# Access_System_Bmduino.net
KiCad netlist of a schematic drawn in Altium Designer
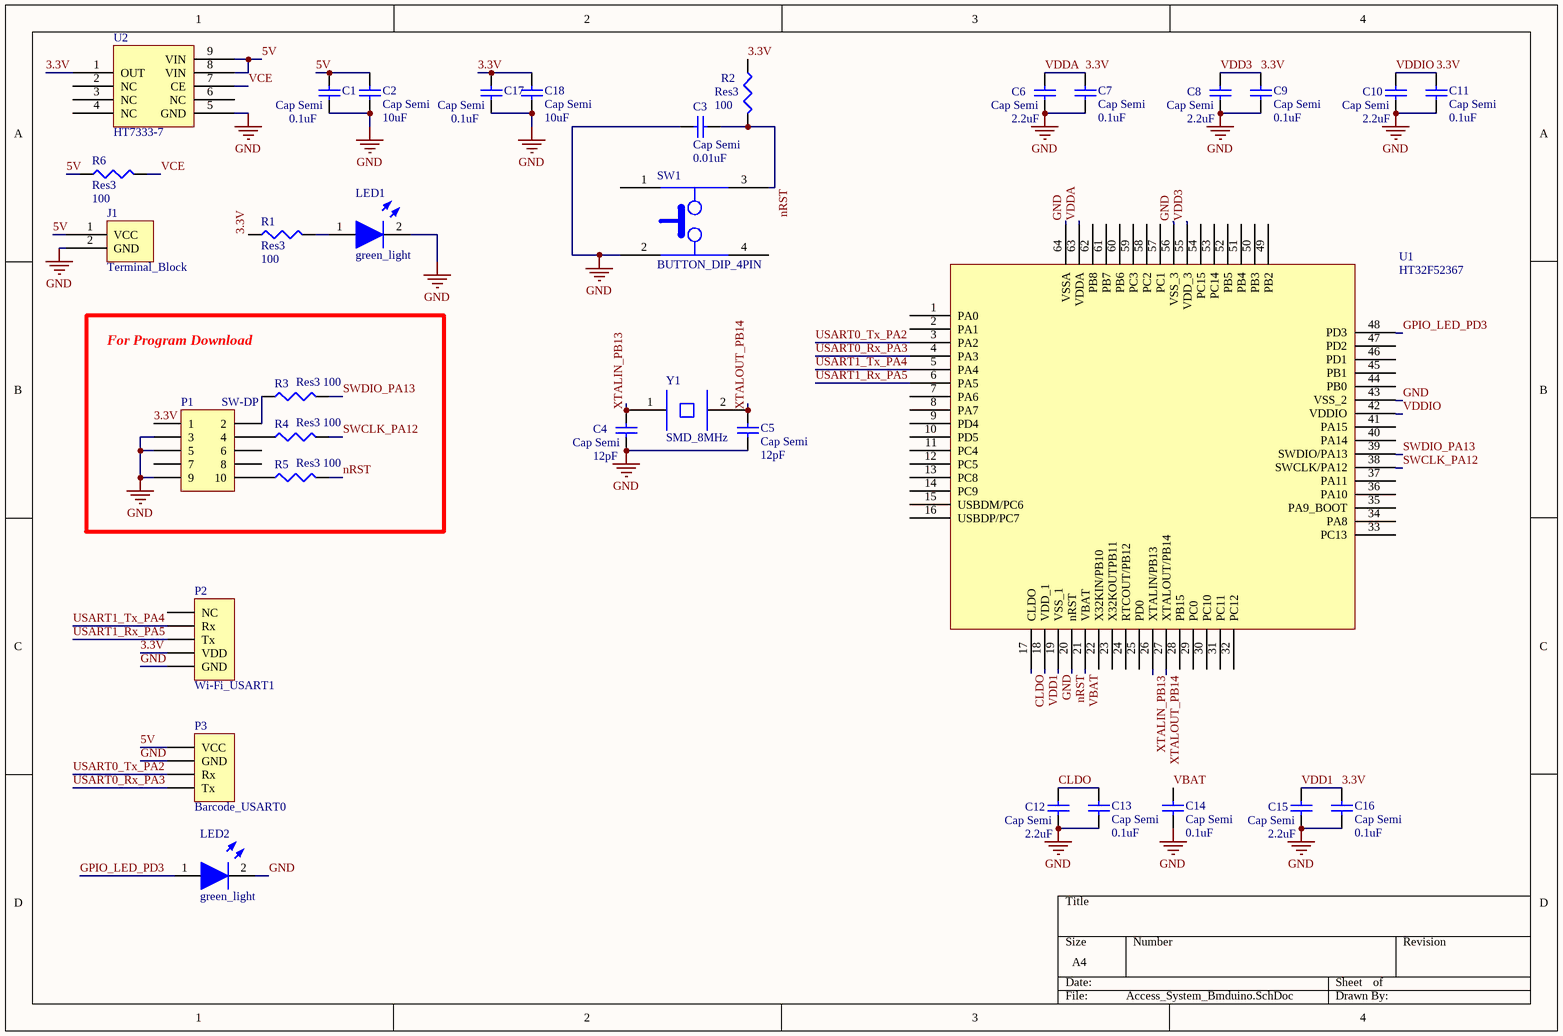
[diagram p0: Access_System_Bmduino.SchDoc]

(export (version "E")
  (design (tool "Eeschema 10.0.6"))
  (components
    (comp (ref "C1")
      (value "Cap Semi")
      (footprint "1608[0603]")
      (description "Capacitor (Semiconductor SIM Model)")
      (fields (field (name "ALTIUM_VALUE") "0.1uF") (field (name "PUBLISHER") "Altium Limited"))
      (libsource (lib "Miscellaneous Devices") (part "Cap Semi"))
    )
    (comp (ref "C2")
      (value "Cap Semi")
      (footprint "1608[0603]")
      (description "Capacitor (Semiconductor SIM Model)")
      (fields (field (name "ALTIUM_VALUE") "10uF") (field (name "PUBLISHER") "Altium Limited"))
      (libsource (lib "Miscellaneous Devices") (part "Cap Semi"))
    )
    (comp (ref "C3")
      (value "Cap Semi")
      (footprint "1608[0603]")
      (description "Capacitor (Semiconductor SIM Model)")
      (fields (field (name "ALTIUM_VALUE") "0.01uF") (field (name "PUBLISHER") "Altium Limited"))
      (libsource (lib "Miscellaneous Devices") (part "Cap Semi"))
    )
    (comp (ref "C4")
      (value "Cap Semi")
      (footprint "1608[0603]")
      (description "Capacitor (Semiconductor SIM Model)")
      (fields (field (name "ALTIUM_VALUE") "12pF") (field (name "PUBLISHER") "Altium Limited"))
      (libsource (lib "Miscellaneous Devices") (part "Cap Semi"))
    )
    (comp (ref "C5")
      (value "Cap Semi")
      (footprint "1608[0603]")
      (description "Capacitor (Semiconductor SIM Model)")
      (fields (field (name "ALTIUM_VALUE") "12pF") (field (name "PUBLISHER") "Altium Limited"))
      (libsource (lib "Miscellaneous Devices") (part "Cap Semi"))
    )
    (comp (ref "C6")
      (value "Cap Semi")
      (footprint "1608[0603]")
      (description "Capacitor (Semiconductor SIM Model)")
      (fields (field (name "ALTIUM_VALUE") "2.2uF") (field (name "PUBLISHER") "Altium Limited"))
      (libsource (lib "Miscellaneous Devices") (part "Cap Semi"))
    )
    (comp (ref "C7")
      (value "Cap Semi")
      (footprint "1608[0603]")
      (description "Capacitor (Semiconductor SIM Model)")
      (fields (field (name "ALTIUM_VALUE") "0.1uF") (field (name "PUBLISHER") "Altium Limited"))
      (libsource (lib "Miscellaneous Devices") (part "Cap Semi"))
    )
    (comp (ref "C8")
      (value "Cap Semi")
      (footprint "1608[0603]")
      (description "Capacitor (Semiconductor SIM Model)")
      (fields (field (name "ALTIUM_VALUE") "2.2uF") (field (name "PUBLISHER") "Altium Limited"))
      (libsource (lib "Miscellaneous Devices") (part "Cap Semi"))
    )
    (comp (ref "C9")
      (value "Cap Semi")
      (footprint "1608[0603]")
      (description "Capacitor (Semiconductor SIM Model)")
      (fields (field (name "ALTIUM_VALUE") "0.1uF") (field (name "PUBLISHER") "Altium Limited"))
      (libsource (lib "Miscellaneous Devices") (part "Cap Semi"))
    )
    (comp (ref "C10")
      (value "Cap Semi")
      (footprint "1608[0603]")
      (description "Capacitor (Semiconductor SIM Model)")
      (fields (field (name "ALTIUM_VALUE") "2.2uF") (field (name "PUBLISHER") "Altium Limited"))
      (libsource (lib "Miscellaneous Devices") (part "Cap Semi"))
    )
    (comp (ref "C11")
      (value "Cap Semi")
      (footprint "1608[0603]")
      (description "Capacitor (Semiconductor SIM Model)")
      (fields (field (name "ALTIUM_VALUE") "0.1uF") (field (name "PUBLISHER") "Altium Limited"))
      (libsource (lib "Miscellaneous Devices") (part "Cap Semi"))
    )
    (comp (ref "C12")
      (value "Cap Semi")
      (footprint "1608[0603]")
      (description "Capacitor (Semiconductor SIM Model)")
      (fields (field (name "ALTIUM_VALUE") "2.2uF") (field (name "PUBLISHER") "Altium Limited"))
      (libsource (lib "Miscellaneous Devices") (part "Cap Semi"))
    )
    (comp (ref "C13")
      (value "Cap Semi")
      (footprint "1608[0603]")
      (description "Capacitor (Semiconductor SIM Model)")
      (fields (field (name "ALTIUM_VALUE") "0.1uF") (field (name "PUBLISHER") "Altium Limited"))
      (libsource (lib "Miscellaneous Devices") (part "Cap Semi"))
    )
    (comp (ref "C14")
      (value "Cap Semi")
      (footprint "1608[0603]")
      (description "Capacitor (Semiconductor SIM Model)")
      (fields (field (name "ALTIUM_VALUE") "0.1uF") (field (name "PUBLISHER") "Altium Limited"))
      (libsource (lib "Miscellaneous Devices") (part "Cap Semi"))
    )
    (comp (ref "C15")
      (value "Cap Semi")
      (footprint "1608[0603]")
      (description "Capacitor (Semiconductor SIM Model)")
      (fields (field (name "ALTIUM_VALUE") "2.2uF") (field (name "PUBLISHER") "Altium Limited"))
      (libsource (lib "Miscellaneous Devices") (part "Cap Semi"))
    )
    (comp (ref "C16")
      (value "Cap Semi")
      (footprint "1608[0603]")
      (description "Capacitor (Semiconductor SIM Model)")
      (fields (field (name "ALTIUM_VALUE") "0.1uF") (field (name "PUBLISHER") "Altium Limited"))
      (libsource (lib "Miscellaneous Devices") (part "Cap Semi"))
    )
    (comp (ref "C17")
      (value "Cap Semi")
      (footprint "1608[0603]")
      (description "Capacitor (Semiconductor SIM Model)")
      (fields (field (name "ALTIUM_VALUE") "0.1uF") (field (name "PUBLISHER") "Altium Limited"))
      (libsource (lib "Miscellaneous Devices") (part "Cap Semi"))
    )
    (comp (ref "C18")
      (value "Cap Semi")
      (footprint "1608[0603]")
      (description "Capacitor (Semiconductor SIM Model)")
      (fields (field (name "ALTIUM_VALUE") "10uF") (field (name "PUBLISHER") "Altium Limited"))
      (libsource (lib "Miscellaneous Devices") (part "Cap Semi"))
    )
    (comp (ref "J1")
      (value "Terminal_Block")
      (footprint "terminal block")
      (libsource (lib "Lab_share") (part "Terminal Block"))
    )
    (comp (ref "LED1")
      (value "green_light")
      (footprint "LED_Green")
      (libsource (lib "Lab_share") (part "LED_Green"))
    )
    (comp (ref "LED2")
      (value "green_light")
      (footprint "LED_Green")
      (libsource (lib "Lab_share") (part "LED_Green"))
    )
    (comp (ref "P1")
      (value "SW-DP")
      (footprint "HDR2X5")
      (description "Header, 5-Pin, Dual row")
      (fields (field (name "PUBLISHER") "Altium Limited"))
      (libsource (lib "Miscellaneous Connectors") (part "Header 5X2"))
    )
    (comp (ref "P2")
      (value "Wi-Fi_USART1")
      (footprint "HDR1X5")
      (description "Header, 5-Pin")
      (fields (field (name "PUBLISHER") "Altium Limited"))
      (libsource (lib "Miscellaneous Connectors") (part "Header 5"))
    )
    (comp (ref "P3")
      (value "Barcode_USART0")
      (footprint "HDR1X4")
      (description "Header, 4-Pin")
      (fields (field (name "PUBLISHER") "Altium Limited"))
      (libsource (lib "Miscellaneous Connectors") (part "Header 4"))
    )
    (comp (ref "R1")
      (value "Res3")
      (footprint "J1-0603")
      (description "Resistor")
      (fields (field (name "ALTIUM_VALUE") "100") (field (name "PUBLISHER") "Altium Limited"))
      (libsource (lib "Miscellaneous Devices") (part "Res3"))
    )
    (comp (ref "R2")
      (value "Res3")
      (footprint "J1-0603")
      (description "Resistor")
      (fields (field (name "ALTIUM_VALUE") "100") (field (name "PUBLISHER") "Altium Limited"))
      (libsource (lib "Miscellaneous Devices") (part "Res3"))
    )
    (comp (ref "R3")
      (value "Res3")
      (footprint "J1-0603")
      (description "Resistor")
      (fields (field (name "ALTIUM_VALUE") "100") (field (name "PUBLISHER") "Altium Limited"))
      (libsource (lib "Miscellaneous Devices") (part "Res3"))
    )
    (comp (ref "R4")
      (value "Res3")
      (footprint "J1-0603")
      (description "Resistor")
      (fields (field (name "ALTIUM_VALUE") "100") (field (name "PUBLISHER") "Altium Limited"))
      (libsource (lib "Miscellaneous Devices") (part "Res3"))
    )
    (comp (ref "R5")
      (value "Res3")
      (footprint "J1-0603")
      (description "Resistor")
      (fields (field (name "ALTIUM_VALUE") "100") (field (name "PUBLISHER") "Altium Limited"))
      (libsource (lib "Miscellaneous Devices") (part "Res3"))
    )
    (comp (ref "R6")
      (value "Res3")
      (footprint "J1-0603")
      (description "Resistor")
      (fields (field (name "ALTIUM_VALUE") "100") (field (name "PUBLISHER") "Altium Limited"))
      (libsource (lib "Miscellaneous Devices") (part "Res3"))
    )
    (comp (ref "SW1")
      (value "BUTTON_DIP_4PIN")
      (footprint "Push_Button")
      (libsource (lib "Lab_share") (part "Push_Button"))
    )
    (comp (ref "U1")
      (value "HT32F52367")
      (footprint "HT32H52367")
      (libsource (lib "Lab_share") (part "HT32F52367"))
    )
    (comp (ref "U2") (value "HT7333-7") (footprint "HT7333") (libsource (lib "Lab_share") (part "HT7333")))
    (comp (ref "Y1")
      (value "SMD_8MHz")
      (footprint "Quartz-Crystal-8MHz")
      (libsource (lib "Lab_share") (part "Quartz_Crystal_8MHz"))
    )
  )
  (nets
    (net (code "1") (name "/3.3V") (class "Default")
      (node (ref "C10") (pin "1") (pinfunction "1_1") (pintype "passive"))
      (node (ref "C11") (pin "2") (pinfunction "2_2") (pintype "passive"))
      (node (ref "C15") (pin "1") (pinfunction "1_1") (pintype "passive"))
      (node (ref "C16") (pin "2") (pinfunction "2_2") (pintype "passive"))
      (node (ref "C17") (pin "2") (pinfunction "2_2") (pintype "passive"))
      (node (ref "C18") (pin "2") (pinfunction "2_2") (pintype "passive"))
      (node (ref "C6") (pin "1") (pinfunction "1_1") (pintype "passive"))
      (node (ref "C7") (pin "2") (pinfunction "2_2") (pintype "passive"))
      (node (ref "C8") (pin "1") (pinfunction "1_1") (pintype "passive"))
      (node (ref "C9") (pin "2") (pinfunction "2_2") (pintype "passive"))
      (node (ref "P1") (pin "1") (pinfunction "1_1") (pintype "passive"))
      (node (ref "P2") (pin "4") (pinfunction "VDD_4") (pintype "passive"))
      (node (ref "R1") (pin "1") (pinfunction "1_1") (pintype "passive"))
      (node (ref "R2") (pin "1") (pinfunction "1_1") (pintype "passive"))
      (node (ref "U1") (pin "18") (pinfunction "VDD_1_18") (pintype "passive"))
      (node (ref "U1") (pin "42") (pinfunction "VDDIO_42") (pintype "passive"))
      (node (ref "U1") (pin "55") (pinfunction "VDD_3_55") (pintype "passive"))
      (node (ref "U1") (pin "63") (pinfunction "VDDA_63") (pintype "passive"))
      (node (ref "U2") (pin "1") (pinfunction "OUT_1") (pintype "passive"))
    )
    (net (code "2") (name "/5V") (class "Default")
      (node (ref "C1") (pin "2") (pinfunction "2_2") (pintype "passive"))
      (node (ref "C2") (pin "2") (pinfunction "2_2") (pintype "passive"))
      (node (ref "J1") (pin "1") (pinfunction "VCC_1") (pintype "passive"))
      (node (ref "P3") (pin "1") (pinfunction "VCC_1") (pintype "passive"))
      (node (ref "R6") (pin "1") (pinfunction "1_1") (pintype "passive"))
      (node (ref "U2") (pin "8") (pinfunction "VIN_8") (pintype "passive"))
      (node (ref "U2") (pin "9") (pinfunction "VIN_9") (pintype "passive"))
    )
    (net (code "3") (name "/CLDO") (class "Default")
      (node (ref "C12") (pin "1") (pinfunction "1_1") (pintype "passive"))
      (node (ref "C13") (pin "2") (pinfunction "2_2") (pintype "passive"))
      (node (ref "U1") (pin "17") (pinfunction "CLDO_17") (pintype "passive"))
    )
    (net (code "4") (name "/GPIO_LED_PD3") (class "Default")
      (node (ref "LED2") (pin "1") (pintype "passive"))
      (node (ref "U1") (pin "48") (pinfunction "PD3_48") (pintype "passive"))
    )
    (net (code "5") (name "/SWCLK_PA12") (class "Default")
      (node (ref "R4") (pin "2") (pinfunction "2_2") (pintype "passive"))
      (node (ref "U1") (pin "38") (pinfunction "SWCLK/PA12_38") (pintype "passive"))
    )
    (net (code "6") (name "/SWDIO_PA13") (class "Default")
      (node (ref "R3") (pin "2") (pinfunction "2_2") (pintype "passive"))
      (node (ref "U1") (pin "39") (pinfunction "SWDIO/PA13_39") (pintype "passive"))
    )
    (net (code "7") (name "/USART0_Rx_PA3") (class "Default")
      (node (ref "P3") (pin "4") (pinfunction "Tx_4") (pintype "passive"))
      (node (ref "U1") (pin "4") (pinfunction "PA3_4") (pintype "passive"))
    )
    (net (code "8") (name "/USART0_Tx_PA2") (class "Default")
      (node (ref "P3") (pin "3") (pinfunction "Rx_3") (pintype "passive"))
      (node (ref "U1") (pin "3") (pinfunction "PA2_3") (pintype "passive"))
    )
    (net (code "9") (name "/USART1_Rx_PA5") (class "Default")
      (node (ref "P2") (pin "3") (pinfunction "Tx_3") (pintype "passive"))
      (node (ref "U1") (pin "6") (pinfunction "PA5_6") (pintype "passive"))
    )
    (net (code "10") (name "/USART1_Tx_PA4") (class "Default")
      (node (ref "P2") (pin "2") (pinfunction "Rx_2") (pintype "passive"))
      (node (ref "U1") (pin "5") (pinfunction "PA4_5") (pintype "passive"))
    )
    (net (code "11") (name "/VBAT") (class "Default")
      (node (ref "C14") (pin "2") (pinfunction "2_2") (pintype "passive"))
      (node (ref "U1") (pin "21") (pinfunction "VBAT_21") (pintype "passive"))
    )
    (net (code "12") (name "/VCE") (class "Default")
      (node (ref "R6") (pin "2") (pinfunction "2_2") (pintype "passive"))
      (node (ref "U2") (pin "7") (pinfunction "CE_7") (pintype "passive"))
    )
    (net (code "13") (name "/XTALIN_PB13") (class "Default")
      (node (ref "C4") (pin "1") (pinfunction "1_1") (pintype "passive"))
      (node (ref "U1") (pin "26") (pinfunction "XTALIN/PB13_26") (pintype "passive"))
      (node (ref "Y1") (pin "1") (pintype "passive"))
    )
    (net (code "14") (name "/XTALOUT_PB14") (class "Default")
      (node (ref "C5") (pin "2") (pinfunction "2_2") (pintype "passive"))
      (node (ref "U1") (pin "27") (pinfunction "XTALOUT/PB14_27") (pintype "passive"))
      (node (ref "Y1") (pin "2") (pintype "passive"))
    )
    (net (code "15") (name "/nRST") (class "Default")
      (node (ref "C3") (pin "1") (pinfunction "1_1") (pintype "passive"))
      (node (ref "R2") (pin "2") (pinfunction "2_2") (pintype "passive"))
      (node (ref "R5") (pin "2") (pinfunction "2_2") (pintype "passive"))
      (node (ref "SW1") (pin "3") (pintype "passive"))
      (node (ref "U1") (pin "20") (pinfunction "nRST_20") (pintype "passive"))
    )
    (net (code "16") (name "GND") (class "Default")
      (node (ref "C1") (pin "1") (pinfunction "1_1") (pintype "passive"))
      (node (ref "C10") (pin "2") (pinfunction "2_2") (pintype "passive"))
      (node (ref "C11") (pin "1") (pinfunction "1_1") (pintype "passive"))
      (node (ref "C12") (pin "2") (pinfunction "2_2") (pintype "passive"))
      (node (ref "C13") (pin "1") (pinfunction "1_1") (pintype "passive"))
      (node (ref "C14") (pin "1") (pinfunction "1_1") (pintype "passive"))
      (node (ref "C15") (pin "2") (pinfunction "2_2") (pintype "passive"))
      (node (ref "C16") (pin "1") (pinfunction "1_1") (pintype "passive"))
      (node (ref "C17") (pin "1") (pinfunction "1_1") (pintype "passive"))
      (node (ref "C18") (pin "1") (pinfunction "1_1") (pintype "passive"))
      (node (ref "C2") (pin "1") (pinfunction "1_1") (pintype "passive"))
      (node (ref "C3") (pin "2") (pinfunction "2_2") (pintype "passive"))
      (node (ref "C4") (pin "2") (pinfunction "2_2") (pintype "passive"))
      (node (ref "C5") (pin "1") (pinfunction "1_1") (pintype "passive"))
      (node (ref "C6") (pin "2") (pinfunction "2_2") (pintype "passive"))
      (node (ref "C7") (pin "1") (pinfunction "1_1") (pintype "passive"))
      (node (ref "C8") (pin "2") (pinfunction "2_2") (pintype "passive"))
      (node (ref "C9") (pin "1") (pinfunction "1_1") (pintype "passive"))
      (node (ref "J1") (pin "2") (pinfunction "GND_2") (pintype "passive"))
      (node (ref "LED1") (pin "2") (pintype "passive"))
      (node (ref "LED2") (pin "2") (pintype "passive"))
      (node (ref "P1") (pin "3") (pinfunction "3_3") (pintype "passive"))
      (node (ref "P1") (pin "5") (pinfunction "5_5") (pintype "passive"))
      (node (ref "P1") (pin "9") (pinfunction "9_9") (pintype "passive"))
      (node (ref "P2") (pin "5") (pinfunction "GND_5") (pintype "passive"))
      (node (ref "P3") (pin "2") (pinfunction "GND_2") (pintype "passive"))
      (node (ref "SW1") (pin "2") (pintype "passive"))
      (node (ref "U1") (pin "19") (pinfunction "VSS_1_19") (pintype "passive"))
      (node (ref "U1") (pin "43") (pinfunction "VSS_2_43") (pintype "passive"))
      (node (ref "U1") (pin "56") (pinfunction "VSS_3_56") (pintype "passive"))
      (node (ref "U1") (pin "64") (pinfunction "VSSA_64") (pintype "passive"))
      (node (ref "U2") (pin "5") (pinfunction "GND_5") (pintype "passive"))
    )
    (net (code "17") (name "Net-(LED1-Pad1)") (class "Default")
      (node (ref "LED1") (pin "1") (pintype "passive"))
      (node (ref "R1") (pin "2") (pinfunction "2_2") (pintype "passive"))
    )
    (net (code "18") (name "Net-(P1-Pad2)") (class "Default")
      (node (ref "P1") (pin "2") (pinfunction "2_2") (pintype "passive"))
      (node (ref "R3") (pin "1") (pinfunction "1_1") (pintype "passive"))
    )
    (net (code "19") (name "Net-(P1-Pad4)") (class "Default")
      (node (ref "P1") (pin "4") (pinfunction "4_4") (pintype "passive"))
      (node (ref "R4") (pin "1") (pinfunction "1_1") (pintype "passive"))
    )
    (net (code "20") (name "Net-(P1-Pad10)") (class "Default")
      (node (ref "P1") (pin "10") (pinfunction "10_10") (pintype "passive"))
      (node (ref "R5") (pin "1") (pinfunction "1_1") (pintype "passive"))
    )
    (net (code "21") (name "unconnected-(P1-Pad6)") (class "Default")
      (node (ref "P1") (pin "6") (pinfunction "6_6") (pintype "passive"))
    )
    (net (code "22") (name "unconnected-(P1-Pad7)") (class "Default")
      (node (ref "P1") (pin "7") (pinfunction "7_7") (pintype "passive"))
    )
    (net (code "23") (name "unconnected-(P1-Pad8)") (class "Default")
      (node (ref "P1") (pin "8") (pinfunction "8_8") (pintype "passive"))
    )
    (net (code "24") (name "unconnected-(P2-NC-Pad1)") (class "Default")
      (node (ref "P2") (pin "1") (pinfunction "NC_1") (pintype "passive"))
    )
    (net (code "25") (name "unconnected-(SW1-Pad1)") (class "Default")
      (node (ref "SW1") (pin "1") (pintype "passive"))
    )
    (net (code "26") (name "unconnected-(SW1-Pad4)") (class "Default")
      (node (ref "SW1") (pin "4") (pintype "passive"))
    )
    (net (code "27") (name "unconnected-(U1-PA0-Pad1)") (class "Default")
      (node (ref "U1") (pin "1") (pinfunction "PA0_1") (pintype "passive"))
    )
    (net (code "28") (name "unconnected-(U1-PA1-Pad2)") (class "Default")
      (node (ref "U1") (pin "2") (pinfunction "PA1_2") (pintype "passive"))
    )
    (net (code "29") (name "unconnected-(U1-PA6-Pad7)") (class "Default")
      (node (ref "U1") (pin "7") (pinfunction "PA6_7") (pintype "passive"))
    )
    (net (code "30") (name "unconnected-(U1-PA7-Pad8)") (class "Default")
      (node (ref "U1") (pin "8") (pinfunction "PA7_8") (pintype "passive"))
    )
    (net (code "31") (name "unconnected-(U1-PA8-Pad34)") (class "Default")
      (node (ref "U1") (pin "34") (pinfunction "PA8_34") (pintype "passive"))
    )
    (net (code "32") (name "unconnected-(U1-PA9_BOOT-Pad35)") (class "Default")
      (node (ref "U1") (pin "35") (pinfunction "PA9_BOOT_35") (pintype "passive"))
    )
    (net (code "33") (name "unconnected-(U1-PA10-Pad36)") (class "Default")
      (node (ref "U1") (pin "36") (pinfunction "PA10_36") (pintype "passive"))
    )
    (net (code "34") (name "unconnected-(U1-PA11-Pad37)") (class "Default")
      (node (ref "U1") (pin "37") (pinfunction "PA11_37") (pintype "passive"))
    )
    (net (code "35") (name "unconnected-(U1-PA14-Pad40)") (class "Default")
      (node (ref "U1") (pin "40") (pinfunction "PA14_40") (pintype "passive"))
    )
    (net (code "36") (name "unconnected-(U1-PA15-Pad41)") (class "Default")
      (node (ref "U1") (pin "41") (pinfunction "PA15_41") (pintype "passive"))
    )
    (net (code "37") (name "unconnected-(U1-PB0-Pad44)") (class "Default")
      (node (ref "U1") (pin "44") (pinfunction "PB0_44") (pintype "passive"))
    )
    (net (code "38") (name "unconnected-(U1-PB1-Pad45)") (class "Default")
      (node (ref "U1") (pin "45") (pinfunction "PB1_45") (pintype "passive"))
    )
    (net (code "39") (name "unconnected-(U1-PB2-Pad49)") (class "Default")
      (node (ref "U1") (pin "49") (pinfunction "PB2_49") (pintype "passive"))
    )
    (net (code "40") (name "unconnected-(U1-PB3-Pad50)") (class "Default")
      (node (ref "U1") (pin "50") (pinfunction "PB3_50") (pintype "passive"))
    )
    (net (code "41") (name "unconnected-(U1-PB4-Pad51)") (class "Default")
      (node (ref "U1") (pin "51") (pinfunction "PB4_51") (pintype "passive"))
    )
    (net (code "42") (name "unconnected-(U1-PB5-Pad52)") (class "Default")
      (node (ref "U1") (pin "52") (pinfunction "PB5_52") (pintype "passive"))
    )
    (net (code "43") (name "unconnected-(U1-PB6-Pad60)") (class "Default")
      (node (ref "U1") (pin "60") (pinfunction "PB6_60") (pintype "passive"))
    )
    (net (code "44") (name "unconnected-(U1-PB7-Pad61)") (class "Default")
      (node (ref "U1") (pin "61") (pinfunction "PB7_61") (pintype "passive"))
    )
    (net (code "45") (name "unconnected-(U1-PB8-Pad62)") (class "Default")
      (node (ref "U1") (pin "62") (pinfunction "PB8_62") (pintype "passive"))
    )
    (net (code "46") (name "unconnected-(U1-PB15-Pad28)") (class "Default")
      (node (ref "U1") (pin "28") (pinfunction "PB15_28") (pintype "passive"))
    )
    (net (code "47") (name "unconnected-(U1-PC0-Pad29)") (class "Default")
      (node (ref "U1") (pin "29") (pinfunction "PC0_29") (pintype "passive"))
    )
    (net (code "48") (name "unconnected-(U1-PC1-Pad57)") (class "Default")
      (node (ref "U1") (pin "57") (pinfunction "PC1_57") (pintype "passive"))
    )
    (net (code "49") (name "unconnected-(U1-PC2-Pad58)") (class "Default")
      (node (ref "U1") (pin "58") (pinfunction "PC2_58") (pintype "passive"))
    )
    (net (code "50") (name "unconnected-(U1-PC3-Pad59)") (class "Default")
      (node (ref "U1") (pin "59") (pinfunction "PC3_59") (pintype "passive"))
    )
    (net (code "51") (name "unconnected-(U1-PC4-Pad11)") (class "Default")
      (node (ref "U1") (pin "11") (pinfunction "PC4_11") (pintype "passive"))
    )
    (net (code "52") (name "unconnected-(U1-PC5-Pad12)") (class "Default")
      (node (ref "U1") (pin "12") (pinfunction "PC5_12") (pintype "passive"))
    )
    (net (code "53") (name "unconnected-(U1-PC8-Pad13)") (class "Default")
      (node (ref "U1") (pin "13") (pinfunction "PC8_13") (pintype "passive"))
    )
    (net (code "54") (name "unconnected-(U1-PC9-Pad14)") (class "Default")
      (node (ref "U1") (pin "14") (pinfunction "PC9_14") (pintype "passive"))
    )
    (net (code "55") (name "unconnected-(U1-PC10-Pad30)") (class "Default")
      (node (ref "U1") (pin "30") (pinfunction "PC10_30") (pintype "passive"))
    )
    (net (code "56") (name "unconnected-(U1-PC11-Pad31)") (class "Default")
      (node (ref "U1") (pin "31") (pinfunction "PC11_31") (pintype "passive"))
    )
    (net (code "57") (name "unconnected-(U1-PC12-Pad32)") (class "Default")
      (node (ref "U1") (pin "32") (pinfunction "PC12_32") (pintype "passive"))
    )
    (net (code "58") (name "unconnected-(U1-PC13-Pad33)") (class "Default")
      (node (ref "U1") (pin "33") (pinfunction "PC13_33") (pintype "passive"))
    )
    (net (code "59") (name "unconnected-(U1-PC14-Pad53)") (class "Default")
      (node (ref "U1") (pin "53") (pinfunction "PC14_53") (pintype "passive"))
    )
    (net (code "60") (name "unconnected-(U1-PC15-Pad54)") (class "Default")
      (node (ref "U1") (pin "54") (pinfunction "PC15_54") (pintype "passive"))
    )
    (net (code "61") (name "unconnected-(U1-PD0-Pad25)") (class "Default")
      (node (ref "U1") (pin "25") (pinfunction "PD0_25") (pintype "passive"))
    )
    (net (code "62") (name "unconnected-(U1-PD1-Pad46)") (class "Default")
      (node (ref "U1") (pin "46") (pinfunction "PD1_46") (pintype "passive"))
    )
    (net (code "63") (name "unconnected-(U1-PD2-Pad47)") (class "Default")
      (node (ref "U1") (pin "47") (pinfunction "PD2_47") (pintype "passive"))
    )
    (net (code "64") (name "unconnected-(U1-PD4-Pad9)") (class "Default")
      (node (ref "U1") (pin "9") (pinfunction "PD4_9") (pintype "passive"))
    )
    (net (code "65") (name "unconnected-(U1-PD5-Pad10)") (class "Default")
      (node (ref "U1") (pin "10") (pinfunction "PD5_10") (pintype "passive"))
    )
    (net (code "66") (name "unconnected-(U1-RTCOUT{slash}PB12-Pad24)") (class "Default")
      (node (ref "U1") (pin "24") (pinfunction "RTCOUT/PB12_24") (pintype "passive"))
    )
    (net (code "67") (name "unconnected-(U1-USBDM{slash}PC6-Pad15)") (class "Default")
      (node (ref "U1") (pin "15") (pinfunction "USBDM/PC6_15") (pintype "passive"))
    )
    (net (code "68") (name "unconnected-(U1-USBDP{slash}PC7-Pad16)") (class "Default")
      (node (ref "U1") (pin "16") (pinfunction "USBDP/PC7_16") (pintype "passive"))
    )
    (net (code "69") (name "unconnected-(U1-X32KIN{slash}PB10-Pad22)") (class "Default")
      (node (ref "U1") (pin "22") (pinfunction "X32KIN/PB10_22") (pintype "passive"))
    )
    (net (code "70") (name "unconnected-(U1-X32KOUTPB11-Pad23)") (class "Default")
      (node (ref "U1") (pin "23") (pinfunction "X32KOUTPB11_23") (pintype "passive"))
    )
    (net (code "71") (name "unconnected-(U2-NC-Pad2)") (class "Default")
      (node (ref "U2") (pin "2") (pinfunction "NC_2") (pintype "passive"))
    )
    (net (code "72") (name "unconnected-(U2-NC-Pad3)") (class "Default")
      (node (ref "U2") (pin "3") (pinfunction "NC_3") (pintype "passive"))
    )
    (net (code "73") (name "unconnected-(U2-NC-Pad4)") (class "Default")
      (node (ref "U2") (pin "4") (pinfunction "NC_4") (pintype "passive"))
    )
    (net (code "74") (name "unconnected-(U2-NC-Pad6)") (class "Default")
      (node (ref "U2") (pin "6") (pinfunction "NC_6") (pintype "passive"))
    )
  )
)
